# BUTTONS.net
KiCad netlist of a schematic drawn in Altium Designer
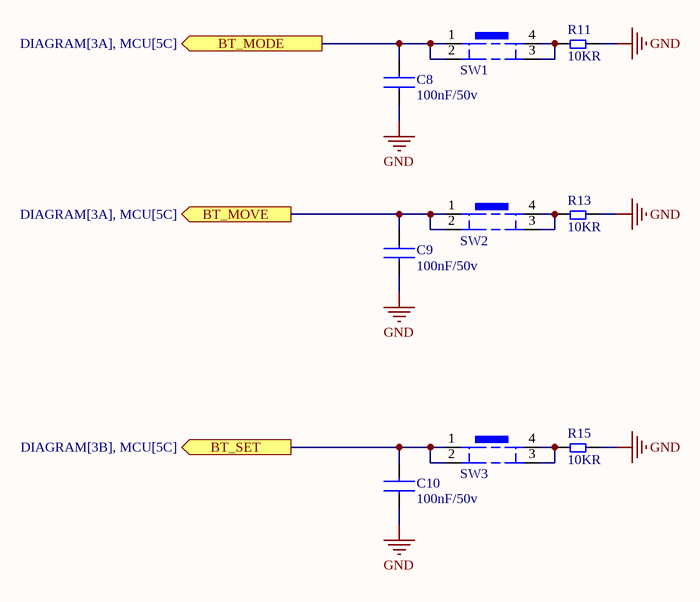
[diagram p0: BUTTONS.SchDoc]

(export (version "E")
  (design (tool "Eeschema 10.0.6"))
  (components
    (comp (ref "C8")
      (value "100nF/50v")
      (footprint "CAP-CER-0805")
      (description "Tụ Gốm 0805 100nF (0.1uF) 50V")
      (libsource (lib "Database_Libs1") (part "CAP-CER"))
    )
    (comp (ref "C9")
      (value "100nF/50v")
      (footprint "CAP-CER-0805")
      (description "Tụ Gốm 0805 100nF (0.1uF) 50V")
      (libsource (lib "Database_Libs1") (part "CAP-CER"))
    )
    (comp (ref "C10")
      (value "100nF/50v")
      (footprint "CAP-CER-0805")
      (description "Tụ Gốm 0805 100nF (0.1uF) 50V")
      (libsource (lib "Database_Libs1") (part "CAP-CER"))
    )
    (comp (ref "R11")
      (value "10KR")
      (footprint "RES-SMD-0805")
      (description "Điện Trở 10 KOhm 0805 1%")
      (libsource (lib "Database_Libs1") (part "RES_SMD"))
    )
    (comp (ref "R13")
      (value "10KR")
      (footprint "RES-SMD-0805")
      (description "Điện Trở 10 KOhm 0805 1%")
      (libsource (lib "Database_Libs1") (part "RES_SMD"))
    )
    (comp (ref "R15")
      (value "10KR")
      (footprint "RES-SMD-0805")
      (description "Điện Trở 10 KOhm 0805 1%")
      (libsource (lib "Database_Libs1") (part "RES_SMD"))
    )
    (comp (ref "SW1")
      (value "0")
      (footprint "Tactice-Switch-TH-12x12-4.5mm")
      (description "Nút Nhấn 6x6mm Cao 6mm 4 Chân Xuyên Lỗ")
      (libsource (lib "Database_Libs1") (part "Tactice Switch"))
    )
    (comp (ref "SW2")
      (value "0")
      (footprint "Tactice-Switch-TH-12x12-4.5mm")
      (description "Nút Nhấn 6x6mm Cao 6mm 4 Chân Xuyên Lỗ")
      (libsource (lib "Database_Libs1") (part "Tactice Switch"))
    )
    (comp (ref "SW3")
      (value "0")
      (footprint "Tactice-Switch-TH-12x12-4.5mm")
      (description "Nút Nhấn 6x6mm Cao 6mm 4 Chân Xuyên Lỗ")
      (libsource (lib "Database_Libs1") (part "Tactice Switch"))
    )
  )
  (nets
    (net (code "1") (name "/BT_MODE") (class "Default")
      (node (ref "C8") (pin "2") (pinfunction "2_2") (pintype "passive"))
      (node (ref "SW1") (pin "1") (pinfunction "1_1") (pintype "passive"))
      (node (ref "SW1") (pin "2") (pinfunction "2_2") (pintype "passive"))
    )
    (net (code "2") (name "/BT_MOVE") (class "Default")
      (node (ref "C9") (pin "2") (pinfunction "2_2") (pintype "passive"))
      (node (ref "SW2") (pin "1") (pinfunction "1_1") (pintype "passive"))
      (node (ref "SW2") (pin "2") (pinfunction "2_2") (pintype "passive"))
    )
    (net (code "3") (name "/BT_SET") (class "Default")
      (node (ref "C10") (pin "2") (pinfunction "2_2") (pintype "passive"))
      (node (ref "SW3") (pin "1") (pinfunction "1_1") (pintype "passive"))
      (node (ref "SW3") (pin "2") (pinfunction "2_2") (pintype "passive"))
    )
    (net (code "4") (name "GND") (class "Default")
      (node (ref "C10") (pin "1") (pinfunction "1_1") (pintype "passive"))
      (node (ref "C8") (pin "1") (pinfunction "1_1") (pintype "passive"))
      (node (ref "C9") (pin "1") (pinfunction "1_1") (pintype "passive"))
      (node (ref "R11") (pin "1") (pinfunction "1_1") (pintype "passive"))
      (node (ref "R13") (pin "1") (pinfunction "1_1") (pintype "passive"))
      (node (ref "R15") (pin "1") (pinfunction "1_1") (pintype "passive"))
    )
    (net (code "5") (name "Net-(R11-Pad2)") (class "Default")
      (node (ref "R11") (pin "2") (pinfunction "2_2") (pintype "passive"))
      (node (ref "SW1") (pin "3") (pinfunction "3_3") (pintype "passive"))
      (node (ref "SW1") (pin "4") (pinfunction "4_4") (pintype "passive"))
    )
    (net (code "6") (name "Net-(R13-Pad2)") (class "Default")
      (node (ref "R13") (pin "2") (pinfunction "2_2") (pintype "passive"))
      (node (ref "SW2") (pin "3") (pinfunction "3_3") (pintype "passive"))
      (node (ref "SW2") (pin "4") (pinfunction "4_4") (pintype "passive"))
    )
    (net (code "7") (name "Net-(R15-Pad2)") (class "Default")
      (node (ref "R15") (pin "2") (pinfunction "2_2") (pintype "passive"))
      (node (ref "SW3") (pin "3") (pinfunction "3_3") (pintype "passive"))
      (node (ref "SW3") (pin "4") (pinfunction "4_4") (pintype "passive"))
    )
  )
)
